# Drone_v1_0.net
KiCad netlist of a schematic drawn in Altium Designer
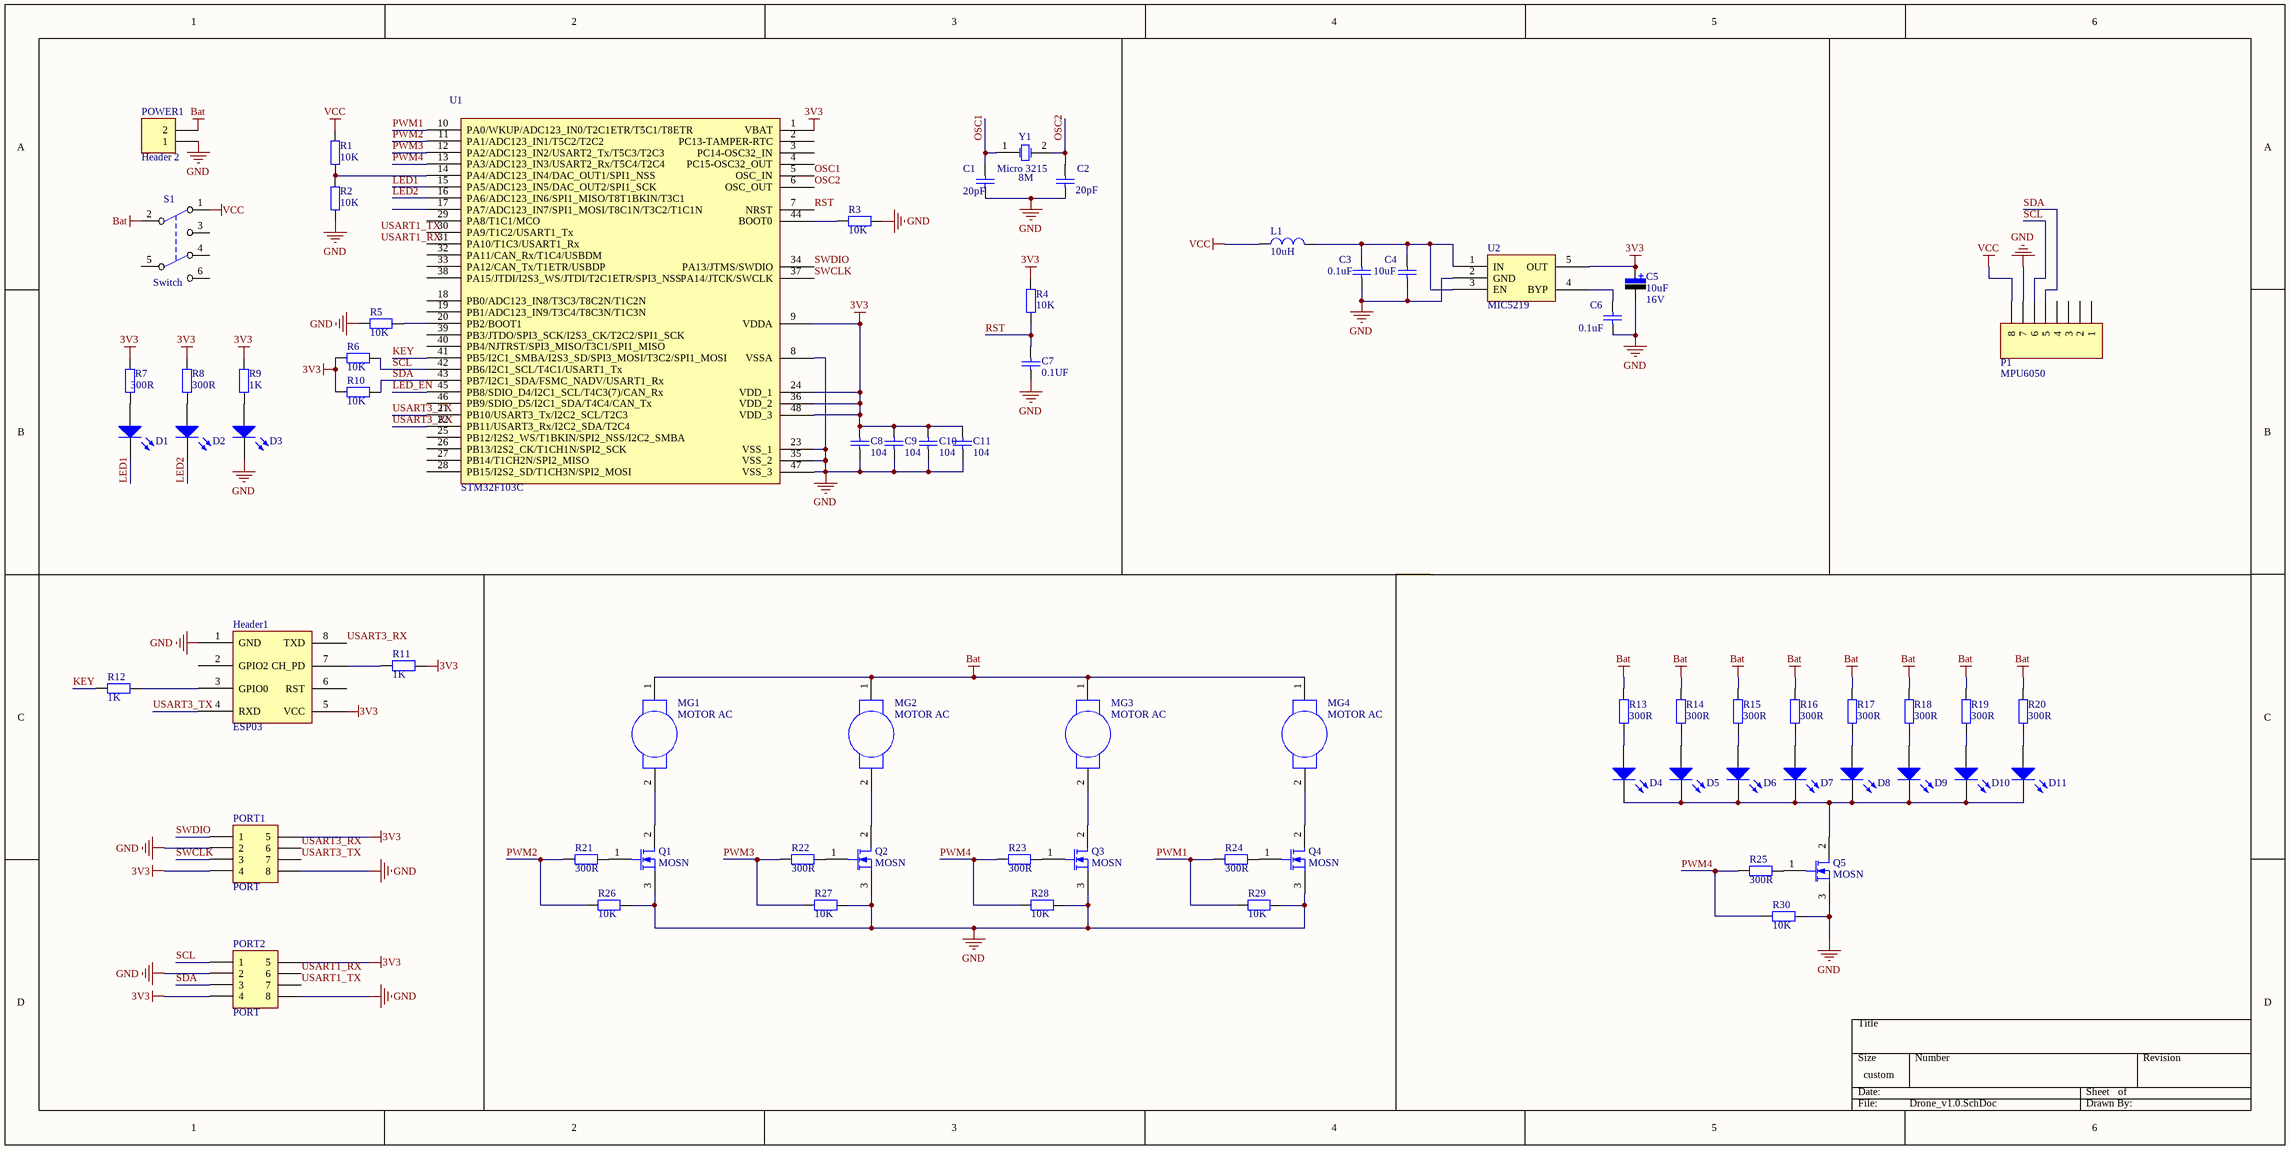
[diagram p0: Drone_v1.0.SchDoc]

(export (version "E")
  (design (tool "Eeschema 10.0.6"))
  (components
    (comp (ref "C1")
      (value "20pF")
      (footprint "0805-2")
      (description "Capacitor")
      (fields (field (name "Comment") "0402 12pF") (field (name "PUBLISHER") "Altium Limited"))
      (libsource (lib "Miscellaneous Devices") (part "Cap"))
    )
    (comp (ref "C2")
      (value "20pF")
      (footprint "0805-2")
      (description "Capacitor")
      (fields (field (name "Comment") "0402 12pF") (field (name "PUBLISHER") "Altium Limited"))
      (libsource (lib "Miscellaneous Devices") (part "Cap"))
    )
    (comp (ref "C3")
      (value "0.1uF")
      (footprint "0805-2")
      (description "Capacitor")
      (fields (field (name "Comment") "0402 12pF") (field (name "PUBLISHER") "Altium Limited"))
      (libsource (lib "Miscellaneous Devices") (part "Cap"))
    )
    (comp (ref "C4")
      (value "10uF")
      (footprint "0805-2")
      (description "Capacitor")
      (fields (field (name "Comment") "0402 12pF") (field (name "PUBLISHER") "Altium Limited"))
      (libsource (lib "Miscellaneous Devices") (part "Cap"))
    )
    (comp (ref "C5")
      (value "10uF")
      (footprint "1206")
      (description "极性电解电容")
      (fields
        (field (name "VOL") "16V")
        (field (name "Comment") "Cap Pol")
        (field (name "PUBLISHER") "Altium Limited")
      )
      (libsource (lib "Fszhang") (part "Cap Pol"))
    )
    (comp (ref "C6")
      (value "0402 12pF")
      (footprint "0805-2")
      (description "Capacitor")
      (fields (field (name "50V") "0.1uF") (field (name "PUBLISHER") "Altium Limited"))
      (libsource (lib "Miscellaneous Devices") (part "Cap"))
    )
    (comp (ref "C7")
      (value "0.1UF")
      (footprint "0805-2")
      (description "无极性电容")
      (fields (field (name "Comment") "Cap") (field (name "PUBLISHER") "Altium Limited"))
      (libsource (lib "Fszhang") (part "Cap"))
    )
    (comp (ref "C8")
      (value "104")
      (footprint "0805-2")
      (description "无极性电容")
      (fields (field (name "Comment") "Cap") (field (name "PUBLISHER") "Altium Limited"))
      (libsource (lib "Fszhang") (part "Cap"))
    )
    (comp (ref "C9")
      (value "104")
      (footprint "0805-2")
      (description "无极性电容")
      (fields (field (name "Comment") "Cap") (field (name "PUBLISHER") "Altium Limited"))
      (libsource (lib "Fszhang") (part "Cap"))
    )
    (comp (ref "C10")
      (value "104")
      (footprint "0805-2")
      (description "无极性电容")
      (fields (field (name "Comment") "Cap") (field (name "PUBLISHER") "Altium Limited"))
      (libsource (lib "Fszhang") (part "Cap"))
    )
    (comp (ref "C11")
      (value "104")
      (footprint "0805-2")
      (description "无极性电容")
      (fields (field (name "Comment") "Cap") (field (name "PUBLISHER") "Altium Limited"))
      (libsource (lib "Fszhang") (part "Cap"))
    )
    (comp (ref "D1")
      (value "LED0")
      (footprint "LED_0805")
      (description "发光二极管")
      (fields (field (name "PUBLISHER") "Altium Limited"))
      (libsource (lib "Fszhang") (part "LED0"))
    )
    (comp (ref "D2")
      (value "LED0")
      (footprint "LED_0805")
      (description "发光二极管")
      (fields (field (name "PUBLISHER") "Altium Limited"))
      (libsource (lib "Fszhang") (part "LED0"))
    )
    (comp (ref "D3")
      (value "LED0")
      (footprint "LED_0805")
      (description "发光二极管")
      (fields (field (name "PUBLISHER") "Altium Limited"))
      (libsource (lib "Fszhang") (part "LED0"))
    )
    (comp (ref "D4")
      (value "LED0")
      (footprint "LED_0805")
      (description "发光二极管")
      (fields (field (name "PUBLISHER") "Altium Limited"))
      (libsource (lib "Fszhang") (part "LED0"))
    )
    (comp (ref "D5")
      (value "LED0")
      (footprint "LED_0805")
      (description "发光二极管")
      (fields (field (name "PUBLISHER") "Altium Limited"))
      (libsource (lib "Fszhang") (part "LED0"))
    )
    (comp (ref "D6")
      (value "LED0")
      (footprint "LED_0805")
      (description "发光二极管")
      (fields (field (name "PUBLISHER") "Altium Limited"))
      (libsource (lib "Fszhang") (part "LED0"))
    )
    (comp (ref "D7")
      (value "LED0")
      (footprint "LED_0805")
      (description "发光二极管")
      (fields (field (name "PUBLISHER") "Altium Limited"))
      (libsource (lib "Fszhang") (part "LED0"))
    )
    (comp (ref "D8")
      (value "LED0")
      (footprint "LED_0805")
      (description "发光二极管")
      (fields (field (name "PUBLISHER") "Altium Limited"))
      (libsource (lib "Fszhang") (part "LED0"))
    )
    (comp (ref "D9")
      (value "LED0")
      (footprint "LED_0805")
      (description "发光二极管")
      (fields (field (name "PUBLISHER") "Altium Limited"))
      (libsource (lib "Fszhang") (part "LED0"))
    )
    (comp (ref "D10")
      (value "LED0")
      (footprint "LED_0805")
      (description "发光二极管")
      (fields (field (name "PUBLISHER") "Altium Limited"))
      (libsource (lib "Fszhang") (part "LED0"))
    )
    (comp (ref "D11")
      (value "LED0")
      (footprint "LED_0805")
      (description "发光二极管")
      (fields (field (name "PUBLISHER") "Altium Limited"))
      (libsource (lib "Fszhang") (part "LED0"))
    )
    (comp (ref "Header1")
      (value "ESP03")
      (footprint "PCBComponent_1")
      (libsource (lib "Header4") (part "Hearder"))
    )
    (comp (ref "L1")
      (value "10uH")
      (footprint "0805-1")
      (description "电感")
      (fields (field (name "Comment") "Inductor") (field (name "PUBLISHER") "Altium Limited"))
      (libsource (lib "Fszhang") (part "Inductor"))
    )
    (comp (ref "MG1") (value "MOTOR AC") (footprint "Motor") (libsource (lib "杂元件库") (part "MOTOR AC")))
    (comp (ref "MG2") (value "MOTOR AC") (footprint "Motor") (libsource (lib "杂元件库") (part "MOTOR AC")))
    (comp (ref "MG3") (value "MOTOR AC") (footprint "Motor") (libsource (lib "杂元件库") (part "MOTOR AC")))
    (comp (ref "MG4") (value "MOTOR AC") (footprint "Motor") (libsource (lib "杂元件库") (part "MOTOR AC")))
    (comp (ref "P1")
      (value "MPU6050")
      (footprint "HDR1X8")
      (description "Header, 8-Pin")
      (fields (field (name "PUBLISHER") "Altium Limited"))
      (libsource (lib "Miscellaneous Connectors") (part "Header 8"))
    )
    (comp (ref "PORT1")
      (value "PORT")
      (footprint "HDR2X4_CEN")
      (description "Header, 4-Pin, Dual row")
      (fields (field (name "PUBLISHER") "Altium Limited"))
      (libsource (lib "Miscellaneous Connectors") (part "Header 4X2A"))
    )
    (comp (ref "PORT2")
      (value "PORT")
      (footprint "HDR2X4_CEN")
      (description "Header, 4-Pin, Dual row")
      (fields (field (name "PUBLISHER") "Altium Limited"))
      (libsource (lib "Miscellaneous Connectors") (part "Header 4X2A"))
    )
    (comp (ref "POWER1")
      (value "Header 2")
      (footprint "HDR1X2")
      (description "Header, 2-Pin")
      (fields (field (name "PUBLISHER") "Altium Limited"))
      (libsource (lib "Miscellaneous Connectors") (part "Header 2"))
    )
    (comp (ref "Q1") (value "MOSN") (footprint "PCBComponent_1") (libsource (lib "MOS-N") (part "SI2302")))
    (comp (ref "Q2") (value "MOSN") (footprint "PCBComponent_1") (libsource (lib "MOS-N") (part "SI2302")))
    (comp (ref "Q3") (value "MOSN") (footprint "PCBComponent_1") (libsource (lib "MOS-N") (part "SI2302")))
    (comp (ref "Q4") (value "MOSN") (footprint "PCBComponent_1") (libsource (lib "MOS-N") (part "SI2302")))
    (comp (ref "Q5") (value "MOSN") (footprint "PCBComponent_1") (libsource (lib "MOS-N") (part "SI2302")))
    (comp (ref "R1")
      (value "10K")
      (footprint "0805-2")
      (description "贴片电阻")
      (fields (field (name "Comment") "Res1") (field (name "PUBLISHER") "Altium Limited"))
      (libsource (lib "") (part "Res1_3"))
    )
    (comp (ref "R2")
      (value "10K")
      (footprint "0805-2")
      (description "贴片电阻")
      (fields (field (name "Comment") "Res1") (field (name "PUBLISHER") "Altium Limited"))
      (libsource (lib "") (part "Res1_1"))
    )
    (comp (ref "R3")
      (value "10K")
      (footprint "0805-2")
      (description "贴片电阻")
      (fields (field (name "Comment") "Res1") (field (name "PUBLISHER") "Altium Limited"))
      (libsource (lib "") (part "Res1_2"))
    )
    (comp (ref "R4")
      (value "10K")
      (footprint "0805-2")
      (description "贴片电阻")
      (fields (field (name "Comment") "Res1") (field (name "PUBLISHER") "Altium Limited"))
      (libsource (lib "") (part "Res1_3"))
    )
    (comp (ref "R5")
      (value "10K")
      (footprint "0805-2")
      (description "贴片电阻")
      (fields (field (name "Comment") "Res1") (field (name "PUBLISHER") "Altium Limited"))
      (libsource (lib "Fszhang") (part "Res1"))
    )
    (comp (ref "R6")
      (value "10K")
      (footprint "0805-2")
      (description "贴片电阻")
      (fields (field (name "Comment") "Res1") (field (name "PUBLISHER") "Altium Limited"))
      (libsource (lib "Fszhang") (part "Res1"))
    )
    (comp (ref "R7")
      (value "300R")
      (footprint "0805-2")
      (description "贴片电阻")
      (fields (field (name "Comment") "Res1") (field (name "PUBLISHER") "Altium Limited"))
      (libsource (lib "") (part "Res1_3"))
    )
    (comp (ref "R8")
      (value "300R")
      (footprint "0805-2")
      (description "贴片电阻")
      (fields (field (name "Comment") "Res1") (field (name "PUBLISHER") "Altium Limited"))
      (libsource (lib "") (part "Res1_3"))
    )
    (comp (ref "R9")
      (value "1K")
      (footprint "0805-2")
      (description "贴片电阻")
      (fields (field (name "Comment") "Res1") (field (name "PUBLISHER") "Altium Limited"))
      (libsource (lib "") (part "Res1_3"))
    )
    (comp (ref "R10")
      (value "10K")
      (footprint "0805-2")
      (description "贴片电阻")
      (fields (field (name "Comment") "Res1") (field (name "PUBLISHER") "Altium Limited"))
      (libsource (lib "Fszhang") (part "Res1"))
    )
    (comp (ref "R11")
      (value "1K")
      (footprint "0805-2")
      (description "贴片电阻")
      (fields (field (name "Comment") "Res1") (field (name "PUBLISHER") "Altium Limited"))
      (libsource (lib "Fszhang") (part "Res1"))
    )
    (comp (ref "R12")
      (value "1K")
      (footprint "0805-2")
      (description "贴片电阻")
      (fields (field (name "Comment") "Res1") (field (name "PUBLISHER") "Altium Limited"))
      (libsource (lib "Fszhang") (part "Res1"))
    )
    (comp (ref "R13")
      (value "300R")
      (footprint "0805-2")
      (description "贴片电阻")
      (fields (field (name "Comment") "Res1") (field (name "PUBLISHER") "Altium Limited"))
      (libsource (lib "") (part "Res1_1"))
    )
    (comp (ref "R14")
      (value "300R")
      (footprint "0805-2")
      (description "贴片电阻")
      (fields (field (name "Comment") "Res1") (field (name "PUBLISHER") "Altium Limited"))
      (libsource (lib "") (part "Res1_1"))
    )
    (comp (ref "R15")
      (value "300R")
      (footprint "0805-2")
      (description "贴片电阻")
      (fields (field (name "Comment") "Res1") (field (name "PUBLISHER") "Altium Limited"))
      (libsource (lib "") (part "Res1_1"))
    )
    (comp (ref "R16")
      (value "300R")
      (footprint "0805-2")
      (description "贴片电阻")
      (fields (field (name "Comment") "Res1") (field (name "PUBLISHER") "Altium Limited"))
      (libsource (lib "") (part "Res1_1"))
    )
    (comp (ref "R17")
      (value "300R")
      (footprint "0805-2")
      (description "贴片电阻")
      (fields (field (name "Comment") "Res1") (field (name "PUBLISHER") "Altium Limited"))
      (libsource (lib "") (part "Res1_1"))
    )
    (comp (ref "R18")
      (value "300R")
      (footprint "0805-2")
      (description "贴片电阻")
      (fields (field (name "Comment") "Res1") (field (name "PUBLISHER") "Altium Limited"))
      (libsource (lib "") (part "Res1_1"))
    )
    (comp (ref "R19")
      (value "300R")
      (footprint "0805-2")
      (description "贴片电阻")
      (fields (field (name "Comment") "Res1") (field (name "PUBLISHER") "Altium Limited"))
      (libsource (lib "") (part "Res1_1"))
    )
    (comp (ref "R20")
      (value "300R")
      (footprint "0805-2")
      (description "贴片电阻")
      (fields (field (name "Comment") "Res1") (field (name "PUBLISHER") "Altium Limited"))
      (libsource (lib "") (part "Res1_1"))
    )
    (comp (ref "R21")
      (value "300R")
      (footprint "0805-2")
      (description "贴片电阻")
      (fields (field (name "Comment") "Res1") (field (name "PUBLISHER") "Altium Limited"))
      (libsource (lib "") (part "Res1_2"))
    )
    (comp (ref "R22")
      (value "300R")
      (footprint "0805-2")
      (description "贴片电阻")
      (fields (field (name "Comment") "Res1") (field (name "PUBLISHER") "Altium Limited"))
      (libsource (lib "") (part "Res1_2"))
    )
    (comp (ref "R23")
      (value "300R")
      (footprint "0805-2")
      (description "贴片电阻")
      (fields (field (name "Comment") "Res1") (field (name "PUBLISHER") "Altium Limited"))
      (libsource (lib "") (part "Res1_2"))
    )
    (comp (ref "R24")
      (value "300R")
      (footprint "0805-2")
      (description "贴片电阻")
      (fields (field (name "Comment") "Res1") (field (name "PUBLISHER") "Altium Limited"))
      (libsource (lib "") (part "Res1_2"))
    )
    (comp (ref "R25")
      (value "300R")
      (footprint "0805-2")
      (description "贴片电阻")
      (fields (field (name "Comment") "Res1") (field (name "PUBLISHER") "Altium Limited"))
      (libsource (lib "") (part "Res1_2"))
    )
    (comp (ref "R26")
      (value "10K")
      (footprint "0805-2")
      (description "贴片电阻")
      (fields (field (name "Comment") "Res1") (field (name "PUBLISHER") "Altium Limited"))
      (libsource (lib "") (part "Res1_2"))
    )
    (comp (ref "R27")
      (value "10K")
      (footprint "0805-2")
      (description "贴片电阻")
      (fields (field (name "Comment") "Res1") (field (name "PUBLISHER") "Altium Limited"))
      (libsource (lib "") (part "Res1_2"))
    )
    (comp (ref "R28")
      (value "10K")
      (footprint "0805-2")
      (description "贴片电阻")
      (fields (field (name "Comment") "Res1") (field (name "PUBLISHER") "Altium Limited"))
      (libsource (lib "") (part "Res1_2"))
    )
    (comp (ref "R29")
      (value "10K")
      (footprint "0805-2")
      (description "贴片电阻")
      (fields (field (name "Comment") "Res1") (field (name "PUBLISHER") "Altium Limited"))
      (libsource (lib "") (part "Res1_2"))
    )
    (comp (ref "R30")
      (value "10K")
      (footprint "0805-2")
      (description "贴片电阻")
      (fields (field (name "Comment") "Res1") (field (name "PUBLISHER") "Altium Limited"))
      (libsource (lib "") (part "Res1_2"))
    )
    (comp (ref "S1") (value "Switch") (footprint "开关") (libsource (lib "开关") (part "双刀双柄开关")))
    (comp (ref "U1")
      (value "STM32F103C")
      (footprint "LQFP-48_M")
      (description "STM32单片机48引脚")
      (libsource (lib "Fszhang") (part "STM32F103C"))
    )
    (comp (ref "U2") (value "MIC5219") (footprint "SOT25-5") (libsource (lib "MIC5219") (part "MIC5219")))
    (comp (ref "Y1")
      (value "Micro 3215")
      (footprint "XTAL5")
      (description "Crystal Oscillator")
      (fields (field (name "ALTIUM_VALUE") "8M"))
      (libsource (lib "Miscellaneous Devices") (part "XTAL"))
    )
  )
  (nets
    (net (code "1") (name "/KEY") (class "Default")
      (node (ref "R12") (pin "1") (pinfunction "1_1") (pintype "passive"))
      (node (ref "U1") (pin "41") (pinfunction "PB5/I2C1_SMBA/I2S3_SD/SPI3_MOSI/T3C2/SPI1_MOSI_41") (pintype "passive"))
    )
    (net (code "2") (name "/LED1") (class "Default")
      (node (ref "D1") (pin "2") (pinfunction "K_2") (pintype "passive"))
      (node (ref "U1") (pin "15") (pinfunction "PA5/ADC123_IN5/DAC_OUT2/SPI1_SCK_15") (pintype "passive"))
    )
    (net (code "3") (name "/LED2") (class "Default")
      (node (ref "D2") (pin "2") (pinfunction "K_2") (pintype "passive"))
      (node (ref "U1") (pin "16") (pinfunction "PA6/ADC123_IN6/SPI1_MISO/T8T1BKIN/T3C1_16") (pintype "passive"))
    )
    (net (code "4") (name "/LED_EN") (class "Default")
      (node (ref "U1") (pin "45") (pinfunction "PB8/SDIO_D4/I2C1_SCL/T4C3(7)/CAN_Rx_45") (pintype "passive"))
    )
    (net (code "5") (name "/OSC1") (class "Default")
      (node (ref "C1") (pin "1") (pinfunction "1_1") (pintype "passive"))
      (node (ref "U1") (pin "5") (pinfunction "OSC_IN_5") (pintype "passive"))
      (node (ref "Y1") (pin "1") (pinfunction "OSC1_1") (pintype "passive"))
    )
    (net (code "6") (name "/OSC2") (class "Default")
      (node (ref "C2") (pin "2") (pinfunction "2_2") (pintype "passive"))
      (node (ref "U1") (pin "6") (pinfunction "OSC_OUT_6") (pintype "passive"))
      (node (ref "Y1") (pin "2") (pinfunction "OSC2_2") (pintype "passive"))
    )
    (net (code "7") (name "/PWM1") (class "Default")
      (node (ref "R24") (pin "2") (pinfunction "2_2") (pintype "passive"))
      (node (ref "R29") (pin "2") (pinfunction "2_2") (pintype "passive"))
      (node (ref "U1") (pin "10") (pinfunction "PA0/WKUP/ADC123_IN0/T2C1ETR/T5C1/T8ETR_10") (pintype "passive"))
    )
    (net (code "8") (name "/PWM2") (class "Default")
      (node (ref "R21") (pin "2") (pinfunction "2_2") (pintype "passive"))
      (node (ref "R26") (pin "2") (pinfunction "2_2") (pintype "passive"))
      (node (ref "U1") (pin "11") (pinfunction "PA1/ADC123_IN1/T5C2/T2C2_11") (pintype "passive"))
    )
    (net (code "9") (name "/PWM3") (class "Default")
      (node (ref "R22") (pin "2") (pinfunction "2_2") (pintype "passive"))
      (node (ref "R27") (pin "2") (pinfunction "2_2") (pintype "passive"))
      (node (ref "U1") (pin "12") (pinfunction "PA2/ADC123_IN2/USART2_Tx/T5C3/T2C3_12") (pintype "passive"))
    )
    (net (code "10") (name "/PWM4") (class "Default")
      (node (ref "R23") (pin "2") (pinfunction "2_2") (pintype "passive"))
      (node (ref "R25") (pin "2") (pinfunction "2_2") (pintype "passive"))
      (node (ref "R28") (pin "2") (pinfunction "2_2") (pintype "passive"))
      (node (ref "R30") (pin "2") (pinfunction "2_2") (pintype "passive"))
      (node (ref "U1") (pin "13") (pinfunction "PA3/ADC123_IN3/USART2_Rx/T5C4/T2C4_13") (pintype "passive"))
    )
    (net (code "11") (name "/RST") (class "Default")
      (node (ref "C7") (pin "1") (pinfunction "1_1") (pintype "passive"))
      (node (ref "R4") (pin "1") (pinfunction "1_1") (pintype "passive"))
      (node (ref "U1") (pin "7") (pinfunction "NRST_7") (pintype "passive"))
    )
    (net (code "12") (name "/SCL") (class "Default")
      (node (ref "P1") (pin "6") (pinfunction "6_6") (pintype "passive"))
      (node (ref "PORT2") (pin "1") (pinfunction "1_1") (pintype "passive"))
      (node (ref "R6") (pin "2") (pinfunction "2_2") (pintype "passive"))
      (node (ref "U1") (pin "42") (pinfunction "PB6/I2C1_SCL/T4C1/USART1_Tx_42") (pintype "passive"))
    )
    (net (code "13") (name "/SDA") (class "Default")
      (node (ref "P1") (pin "5") (pinfunction "5_5") (pintype "passive"))
      (node (ref "PORT2") (pin "3") (pinfunction "3_3") (pintype "passive"))
      (node (ref "R10") (pin "2") (pinfunction "2_2") (pintype "passive"))
      (node (ref "U1") (pin "43") (pinfunction "PB7/I2C1_SDA/FSMC_NADV/USART1_Rx_43") (pintype "passive"))
    )
    (net (code "14") (name "/SWCLK") (class "Default")
      (node (ref "PORT1") (pin "3") (pinfunction "3_3") (pintype "passive"))
      (node (ref "U1") (pin "37") (pinfunction "PA14/JTCK/SWCLK_37") (pintype "passive"))
    )
    (net (code "15") (name "/SWDIO") (class "Default")
      (node (ref "PORT1") (pin "1") (pinfunction "1_1") (pintype "passive"))
      (node (ref "U1") (pin "34") (pinfunction "PA13/JTMS/SWDIO_34") (pintype "passive"))
    )
    (net (code "16") (name "/USART1_RX") (class "Default")
      (node (ref "PORT2") (pin "6") (pinfunction "6_6") (pintype "passive"))
    )
    (net (code "17") (name "/USART1_TX") (class "Default")
      (node (ref "PORT2") (pin "7") (pinfunction "7_7") (pintype "passive"))
    )
    (net (code "18") (name "/USART3_RX") (class "Default")
      (node (ref "Header1") (pin "8") (pinfunction "TXD_8") (pintype "passive"))
      (node (ref "PORT1") (pin "6") (pinfunction "6_6") (pintype "passive"))
      (node (ref "U1") (pin "22") (pinfunction "PB11/USART3_Rx/I2C2_SDA/T2C4_22") (pintype "passive"))
    )
    (net (code "19") (name "/USART3_TX") (class "Default")
      (node (ref "Header1") (pin "4") (pinfunction "RXD_4") (pintype "passive"))
      (node (ref "PORT1") (pin "7") (pinfunction "7_7") (pintype "passive"))
      (node (ref "U1") (pin "21") (pinfunction "PB10/USART3_Tx/I2C2_SCL/T2C3_21") (pintype "passive"))
    )
    (net (code "20") (name "3V3") (class "Default")
      (node (ref "C10") (pin "2") (pinfunction "2_2") (pintype "passive"))
      (node (ref "C11") (pin "2") (pinfunction "2_2") (pintype "passive"))
      (node (ref "C5") (pin "1") (pinfunction "1_1") (pintype "passive"))
      (node (ref "C8") (pin "2") (pinfunction "2_2") (pintype "passive"))
      (node (ref "C9") (pin "2") (pinfunction "2_2") (pintype "passive"))
      (node (ref "Header1") (pin "5") (pinfunction "VCC_5") (pintype "passive"))
      (node (ref "PORT1") (pin "4") (pinfunction "4_4") (pintype "passive"))
      (node (ref "PORT1") (pin "5") (pinfunction "5_5") (pintype "passive"))
      (node (ref "PORT2") (pin "4") (pinfunction "4_4") (pintype "passive"))
      (node (ref "PORT2") (pin "5") (pinfunction "5_5") (pintype "passive"))
      (node (ref "R10") (pin "1") (pinfunction "1_1") (pintype "passive"))
      (node (ref "R11") (pin "2") (pinfunction "2_2") (pintype "passive"))
      (node (ref "R4") (pin "2") (pinfunction "2_2") (pintype "passive"))
      (node (ref "R6") (pin "1") (pinfunction "1_1") (pintype "passive"))
      (node (ref "R7") (pin "2") (pinfunction "2_2") (pintype "passive"))
      (node (ref "R8") (pin "2") (pinfunction "2_2") (pintype "passive"))
      (node (ref "R9") (pin "2") (pinfunction "2_2") (pintype "passive"))
      (node (ref "U1") (pin "1") (pinfunction "VBAT_1") (pintype "passive"))
      (node (ref "U1") (pin "24") (pinfunction "VDD_1_24") (pintype "passive"))
      (node (ref "U1") (pin "36") (pinfunction "VDD_2_36") (pintype "passive"))
      (node (ref "U1") (pin "48") (pinfunction "VDD_3_48") (pintype "passive"))
      (node (ref "U1") (pin "9") (pinfunction "VDDA_9") (pintype "passive"))
      (node (ref "U2") (pin "5") (pinfunction "OUT_5") (pintype "passive"))
    )
    (net (code "21") (name "Bat") (class "Default")
      (node (ref "MG1") (pin "1") (pinfunction "1_1") (pintype "passive"))
      (node (ref "MG2") (pin "1") (pinfunction "1_1") (pintype "passive"))
      (node (ref "MG3") (pin "1") (pinfunction "1_1") (pintype "passive"))
      (node (ref "MG4") (pin "1") (pinfunction "1_1") (pintype "passive"))
      (node (ref "POWER1") (pin "2") (pinfunction "2_2") (pintype "passive"))
      (node (ref "R13") (pin "1") (pinfunction "1_1") (pintype "passive"))
      (node (ref "R14") (pin "1") (pinfunction "1_1") (pintype "passive"))
      (node (ref "R15") (pin "1") (pinfunction "1_1") (pintype "passive"))
      (node (ref "R16") (pin "1") (pinfunction "1_1") (pintype "passive"))
      (node (ref "R17") (pin "1") (pinfunction "1_1") (pintype "passive"))
      (node (ref "R18") (pin "1") (pinfunction "1_1") (pintype "passive"))
      (node (ref "R19") (pin "1") (pinfunction "1_1") (pintype "passive"))
      (node (ref "R20") (pin "1") (pinfunction "1_1") (pintype "passive"))
      (node (ref "S1") (pin "2") (pinfunction "COMMON1_2") (pintype "passive"))
    )
    (net (code "22") (name "GND") (class "Default")
      (node (ref "C1") (pin "2") (pinfunction "2_2") (pintype "passive"))
      (node (ref "C10") (pin "1") (pinfunction "1_1") (pintype "passive"))
      (node (ref "C11") (pin "1") (pinfunction "1_1") (pintype "passive"))
      (node (ref "C2") (pin "1") (pinfunction "1_1") (pintype "passive"))
      (node (ref "C3") (pin "2") (pinfunction "2_2") (pintype "passive"))
      (node (ref "C4") (pin "2") (pinfunction "2_2") (pintype "passive"))
      (node (ref "C5") (pin "2") (pinfunction "2_2") (pintype "passive"))
      (node (ref "C6") (pin "2") (pinfunction "2_2") (pintype "passive"))
      (node (ref "C7") (pin "2") (pinfunction "2_2") (pintype "passive"))
      (node (ref "C8") (pin "1") (pinfunction "1_1") (pintype "passive"))
      (node (ref "C9") (pin "1") (pinfunction "1_1") (pintype "passive"))
      (node (ref "D3") (pin "2") (pinfunction "K_2") (pintype "passive"))
      (node (ref "Header1") (pin "1") (pinfunction "GND_1") (pintype "passive"))
      (node (ref "P1") (pin "7") (pinfunction "7_7") (pintype "passive"))
      (node (ref "PORT1") (pin "2") (pinfunction "2_2") (pintype "passive"))
      (node (ref "PORT1") (pin "8") (pinfunction "8_8") (pintype "passive"))
      (node (ref "PORT2") (pin "2") (pinfunction "2_2") (pintype "passive"))
      (node (ref "PORT2") (pin "8") (pinfunction "8_8") (pintype "passive"))
      (node (ref "POWER1") (pin "1") (pinfunction "1_1") (pintype "passive"))
      (node (ref "Q1") (pin "3") (pinfunction "D_3") (pintype "passive"))
      (node (ref "Q2") (pin "3") (pinfunction "D_3") (pintype "passive"))
      (node (ref "Q3") (pin "3") (pinfunction "D_3") (pintype "passive"))
      (node (ref "Q4") (pin "3") (pinfunction "D_3") (pintype "passive"))
      (node (ref "Q5") (pin "3") (pinfunction "D_3") (pintype "passive"))
      (node (ref "R2") (pin "2") (pinfunction "2_2") (pintype "passive"))
      (node (ref "R26") (pin "1") (pinfunction "1_1") (pintype "passive"))
      (node (ref "R27") (pin "1") (pinfunction "1_1") (pintype "passive"))
      (node (ref "R28") (pin "1") (pinfunction "1_1") (pintype "passive"))
      (node (ref "R29") (pin "1") (pinfunction "1_1") (pintype "passive"))
      (node (ref "R3") (pin "1") (pinfunction "1_1") (pintype "passive"))
      (node (ref "R30") (pin "1") (pinfunction "1_1") (pintype "passive"))
      (node (ref "R5") (pin "1") (pinfunction "1_1") (pintype "passive"))
      (node (ref "U1") (pin "23") (pinfunction "VSS_1_23") (pintype "passive"))
      (node (ref "U1") (pin "35") (pinfunction "VSS_2_35") (pintype "passive"))
      (node (ref "U1") (pin "47") (pinfunction "VSS_3_47") (pintype "passive"))
      (node (ref "U1") (pin "8") (pinfunction "VSSA_8") (pintype "passive"))
      (node (ref "U2") (pin "2") (pinfunction "GND_2") (pintype "passive"))
    )
    (net (code "23") (name "Net-(D1-A)") (class "Default")
      (node (ref "D1") (pin "1") (pinfunction "A_1") (pintype "passive"))
      (node (ref "R7") (pin "1") (pinfunction "1_1") (pintype "passive"))
    )
    (net (code "24") (name "Net-(D2-A)") (class "Default")
      (node (ref "D2") (pin "1") (pinfunction "A_1") (pintype "passive"))
      (node (ref "R8") (pin "1") (pinfunction "1_1") (pintype "passive"))
    )
    (net (code "25") (name "Net-(D3-A)") (class "Default")
      (node (ref "D3") (pin "1") (pinfunction "A_1") (pintype "passive"))
      (node (ref "R9") (pin "1") (pinfunction "1_1") (pintype "passive"))
    )
    (net (code "26") (name "Net-(D4-A)") (class "Default")
      (node (ref "D4") (pin "1") (pinfunction "A_1") (pintype "passive"))
      (node (ref "R13") (pin "2") (pinfunction "2_2") (pintype "passive"))
    )
    (net (code "27") (name "Net-(D5-A)") (class "Default")
      (node (ref "D5") (pin "1") (pinfunction "A_1") (pintype "passive"))
      (node (ref "R14") (pin "2") (pinfunction "2_2") (pintype "passive"))
    )
    (net (code "28") (name "Net-(D6-A)") (class "Default")
      (node (ref "D6") (pin "1") (pinfunction "A_1") (pintype "passive"))
      (node (ref "R15") (pin "2") (pinfunction "2_2") (pintype "passive"))
    )
    (net (code "29") (name "Net-(D7-A)") (class "Default")
      (node (ref "D7") (pin "1") (pinfunction "A_1") (pintype "passive"))
      (node (ref "R16") (pin "2") (pinfunction "2_2") (pintype "passive"))
    )
    (net (code "30") (name "Net-(D8-A)") (class "Default")
      (node (ref "D8") (pin "1") (pinfunction "A_1") (pintype "passive"))
      (node (ref "R17") (pin "2") (pinfunction "2_2") (pintype "passive"))
    )
    (net (code "31") (name "Net-(D9-A)") (class "Default")
      (node (ref "D9") (pin "1") (pinfunction "A_1") (pintype "passive"))
      (node (ref "R18") (pin "2") (pinfunction "2_2") (pintype "passive"))
    )
    (net (code "32") (name "Net-(D10-A)") (class "Default")
      (node (ref "D10") (pin "1") (pinfunction "A_1") (pintype "passive"))
      (node (ref "R19") (pin "2") (pinfunction "2_2") (pintype "passive"))
    )
    (net (code "33") (name "Net-(D10-K)") (class "Default")
      (node (ref "D10") (pin "2") (pinfunction "K_2") (pintype "passive"))
      (node (ref "D11") (pin "2") (pinfunction "K_2") (pintype "passive"))
      (node (ref "D4") (pin "2") (pinfunction "K_2") (pintype "passive"))
      (node (ref "D5") (pin "2") (pinfunction "K_2") (pintype "passive"))
      (node (ref "D6") (pin "2") (pinfunction "K_2") (pintype "passive"))
      (node (ref "D7") (pin "2") (pinfunction "K_2") (pintype "passive"))
      (node (ref "D8") (pin "2") (pinfunction "K_2") (pintype "passive"))
      (node (ref "D9") (pin "2") (pinfunction "K_2") (pintype "passive"))
      (node (ref "Q5") (pin "2") (pinfunction "S_2") (pintype "passive"))
    )
    (net (code "34") (name "Net-(D11-A)") (class "Default")
      (node (ref "D11") (pin "1") (pinfunction "A_1") (pintype "passive"))
      (node (ref "R20") (pin "2") (pinfunction "2_2") (pintype "passive"))
    )
    (net (code "35") (name "Net-(Header1-CH_PD)") (class "Default")
      (node (ref "Header1") (pin "7") (pinfunction "CH_PD_7") (pintype "passive"))
      (node (ref "R11") (pin "1") (pinfunction "1_1") (pintype "passive"))
    )
    (net (code "36") (name "Net-(Header1-GPIO0)") (class "Default")
      (node (ref "Header1") (pin "3") (pinfunction "GPIO0_3") (pintype "passive"))
      (node (ref "R12") (pin "2") (pinfunction "2_2") (pintype "passive"))
    )
    (net (code "37") (name "Net-(Q1-G)") (class "Default")
      (node (ref "Q1") (pin "1") (pinfunction "G_1") (pintype "passive"))
      (node (ref "R21") (pin "1") (pinfunction "1_1") (pintype "passive"))
    )
    (net (code "38") (name "Net-(Q1-S)") (class "Default")
      (node (ref "MG1") (pin "2") (pinfunction "2_2") (pintype "passive"))
      (node (ref "Q1") (pin "2") (pinfunction "S_2") (pintype "passive"))
    )
    (net (code "39") (name "Net-(Q2-G)") (class "Default")
      (node (ref "Q2") (pin "1") (pinfunction "G_1") (pintype "passive"))
      (node (ref "R22") (pin "1") (pinfunction "1_1") (pintype "passive"))
    )
    (net (code "40") (name "Net-(Q2-S)") (class "Default")
      (node (ref "MG2") (pin "2") (pinfunction "2_2") (pintype "passive"))
      (node (ref "Q2") (pin "2") (pinfunction "S_2") (pintype "passive"))
    )
    (net (code "41") (name "Net-(Q3-G)") (class "Default")
      (node (ref "Q3") (pin "1") (pinfunction "G_1") (pintype "passive"))
      (node (ref "R23") (pin "1") (pinfunction "1_1") (pintype "passive"))
    )
    (net (code "42") (name "Net-(Q3-S)") (class "Default")
      (node (ref "MG3") (pin "2") (pinfunction "2_2") (pintype "passive"))
      (node (ref "Q3") (pin "2") (pinfunction "S_2") (pintype "passive"))
    )
    (net (code "43") (name "Net-(Q4-G)") (class "Default")
      (node (ref "Q4") (pin "1") (pinfunction "G_1") (pintype "passive"))
      (node (ref "R24") (pin "1") (pinfunction "1_1") (pintype "passive"))
    )
    (net (code "44") (name "Net-(Q4-S)") (class "Default")
      (node (ref "MG4") (pin "2") (pinfunction "2_2") (pintype "passive"))
      (node (ref "Q4") (pin "2") (pinfunction "S_2") (pintype "passive"))
    )
    (net (code "45") (name "Net-(Q5-G)") (class "Default")
      (node (ref "Q5") (pin "1") (pinfunction "G_1") (pintype "passive"))
      (node (ref "R25") (pin "1") (pinfunction "1_1") (pintype "passive"))
    )
    (net (code "46") (name "Net-(U1-BOOT0)") (class "Default")
      (node (ref "R3") (pin "2") (pinfunction "2_2") (pintype "passive"))
      (node (ref "U1") (pin "44") (pinfunction "BOOT0_44") (pintype "passive"))
    )
    (net (code "47") (name "Net-(U1-PA4{slash}ADC123_IN4{slash}DAC_OUT1{slash}SPI1_NSS)") (class "Default")
      (node (ref "R1") (pin "1") (pinfunction "1_1") (pintype "passive"))
      (node (ref "R2") (pin "1") (pinfunction "1_1") (pintype "passive"))
      (node (ref "U1") (pin "14") (pinfunction "PA4/ADC123_IN4/DAC_OUT1/SPI1_NSS_14") (pintype "passive"))
    )
    (net (code "48") (name "Net-(U1-PB2{slash}BOOT1)") (class "Default")
      (node (ref "R5") (pin "2") (pinfunction "2_2") (pintype "passive"))
      (node (ref "U1") (pin "20") (pinfunction "PB2/BOOT1_20") (pintype "passive"))
    )
    (net (code "49") (name "Net-(U2-BYP)") (class "Default")
      (node (ref "C6") (pin "1") (pinfunction "1_1") (pintype "passive"))
      (node (ref "U2") (pin "4") (pinfunction "BYP_4") (pintype "passive"))
    )
    (net (code "50") (name "Net-(U2-EN)") (class "Default")
      (node (ref "C3") (pin "1") (pinfunction "1_1") (pintype "passive"))
      (node (ref "C4") (pin "1") (pinfunction "1_1") (pintype "passive"))
      (node (ref "L1") (pin "2") (pinfunction "2_2") (pintype "passive"))
      (node (ref "U2") (pin "1") (pinfunction "IN_1") (pintype "passive"))
      (node (ref "U2") (pin "3") (pinfunction "EN_3") (pintype "passive"))
    )
    (net (code "51") (name "VCC") (class "Default")
      (node (ref "L1") (pin "1") (pinfunction "1_1") (pintype "passive"))
      (node (ref "P1") (pin "8") (pinfunction "8_8") (pintype "passive"))
      (node (ref "R1") (pin "2") (pinfunction "2_2") (pintype "passive"))
      (node (ref "S1") (pin "1") (pinfunction "NC1_1") (pintype "passive"))
    )
    (net (code "52") (name "unconnected-(Header1-GPIO2-Pad2)") (class "Default")
      (node (ref "Header1") (pin "2") (pinfunction "GPIO2_2") (pintype "passive"))
    )
    (net (code "53") (name "unconnected-(Header1-RST-Pad6)") (class "Default")
      (node (ref "Header1") (pin "6") (pinfunction "RST_6") (pintype "passive"))
    )
    (net (code "54") (name "unconnected-(P1-Pad1)") (class "Default")
      (node (ref "P1") (pin "1") (pinfunction "1_1") (pintype "passive"))
    )
    (net (code "55") (name "unconnected-(P1-Pad2)") (class "Default")
      (node (ref "P1") (pin "2") (pinfunction "2_2") (pintype "passive"))
    )
    (net (code "56") (name "unconnected-(P1-Pad3)") (class "Default")
      (node (ref "P1") (pin "3") (pinfunction "3_3") (pintype "passive"))
    )
    (net (code "57") (name "unconnected-(P1-Pad4)") (class "Default")
      (node (ref "P1") (pin "4") (pinfunction "4_4") (pintype "passive"))
    )
    (net (code "58") (name "unconnected-(S1-COMMON2-Pad5)") (class "Default")
      (node (ref "S1") (pin "5") (pinfunction "COMMON2_5") (pintype "passive"))
    )
    (net (code "59") (name "unconnected-(S1-NC2-Pad4)") (class "Default")
      (node (ref "S1") (pin "4") (pinfunction "NC2_4") (pintype "passive"))
    )
    (net (code "60") (name "unconnected-(S1-NO1-Pad3)") (class "Default")
      (node (ref "S1") (pin "3") (pinfunction "NO1_3") (pintype "passive"))
    )
    (net (code "61") (name "unconnected-(S1-NO2-Pad6)") (class "Default")
      (node (ref "S1") (pin "6") (pinfunction "NO2_6") (pintype "passive"))
    )
    (net (code "62") (name "unconnected-(U1-PA7{slash}ADC123_IN7{slash}SPI1_MOSI{slash}T8C1N{slash}T3C2{slash}T1C1N-Pad17)") (class "Default")
      (node (ref "U1") (pin "17") (pinfunction "PA7/ADC123_IN7/SPI1_MOSI/T8C1N/T3C2/T1C1N_17") (pintype "passive"))
    )
    (net (code "63") (name "unconnected-(U1-PA8{slash}T1C1{slash}MCO-Pad29)") (class "Default")
      (node (ref "U1") (pin "29") (pinfunction "PA8/T1C1/MCO_29") (pintype "passive"))
    )
    (net (code "64") (name "unconnected-(U1-PA9{slash}T1C2{slash}USART1_Tx-Pad30)") (class "Default")
      (node (ref "U1") (pin "30") (pinfunction "PA9/T1C2/USART1_Tx_30") (pintype "passive"))
    )
    (net (code "65") (name "unconnected-(U1-PA10{slash}T1C3{slash}USART1_Rx-Pad31)") (class "Default")
      (node (ref "U1") (pin "31") (pinfunction "PA10/T1C3/USART1_Rx_31") (pintype "passive"))
    )
    (net (code "66") (name "unconnected-(U1-PA11{slash}CAN_Rx{slash}T1C4{slash}USBDM-Pad32)") (class "Default")
      (node (ref "U1") (pin "32") (pinfunction "PA11/CAN_Rx/T1C4/USBDM_32") (pintype "passive"))
    )
    (net (code "67") (name "unconnected-(U1-PA12{slash}CAN_Tx{slash}T1ETR{slash}USBDP-Pad33)") (class "Default")
      (node (ref "U1") (pin "33") (pinfunction "PA12/CAN_Tx/T1ETR/USBDP_33") (pintype "passive"))
    )
    (net (code "68") (name "unconnected-(U1-PA15{slash}JTDI{slash}I2S3_WS{slash}JTDI{slash}T2C1ETR{slash}SPI3_NSS-Pad38)") (class "Default")
      (node (ref "U1") (pin "38") (pinfunction "PA15/JTDI/I2S3_WS/JTDI/T2C1ETR/SPI3_NSS_38") (pintype "passive"))
    )
    (net (code "69") (name "unconnected-(U1-PB0{slash}ADC123_IN8{slash}T3C3{slash}T8C2N{slash}T1C2N-Pad18)") (class "Default")
      (node (ref "U1") (pin "18") (pinfunction "PB0/ADC123_IN8/T3C3/T8C2N/T1C2N_18") (pintype "passive"))
    )
    (net (code "70") (name "unconnected-(U1-PB1{slash}ADC123_IN9{slash}T3C4{slash}T8C3N{slash}T1C3N-Pad19)") (class "Default")
      (node (ref "U1") (pin "19") (pinfunction "PB1/ADC123_IN9/T3C4/T8C3N/T1C3N_19") (pintype "passive"))
    )
    (net (code "71") (name "unconnected-(U1-PB3{slash}JTDO{slash}SPI3_SCK{slash}I2S3_CK{slash}T2C2{slash}SPI1_SCK-Pad39)") (class "Default")
      (node (ref "U1") (pin "39") (pinfunction "PB3/JTDO/SPI3_SCK/I2S3_CK/T2C2/SPI1_SCK_39") (pintype "passive"))
    )
    (net (code "72") (name "unconnected-(U1-PB4{slash}NJTRST{slash}SPI3_MISO{slash}T3C1{slash}SPI1_MISO-Pad40)") (class "Default")
      (node (ref "U1") (pin "40") (pinfunction "PB4/NJTRST/SPI3_MISO/T3C1/SPI1_MISO_40") (pintype "passive"))
    )
    (net (code "73") (name "unconnected-(U1-PB9{slash}SDIO_D5{slash}I2C1_SDA{slash}T4C4{slash}CAN_Tx-Pad46)") (class "Default")
      (node (ref "U1") (pin "46") (pinfunction "PB9/SDIO_D5/I2C1_SDA/T4C4/CAN_Tx_46") (pintype "passive"))
    )
    (net (code "74") (name "unconnected-(U1-PB12{slash}I2S2_WS{slash}T1BKIN{slash}SPI2_NSS{slash}I2C2_SMBA-Pad25)") (class "Default")
      (node (ref "U1") (pin "25") (pinfunction "PB12/I2S2_WS/T1BKIN/SPI2_NSS/I2C2_SMBA_25") (pintype "passive"))
    )
    (net (code "75") (name "unconnected-(U1-PB13{slash}I2S2_CK{slash}T1CH1N{slash}SPI2_SCK-Pad26)") (class "Default")
      (node (ref "U1") (pin "26") (pinfunction "PB13/I2S2_CK/T1CH1N/SPI2_SCK_26") (pintype "passive"))
    )
    (net (code "76") (name "unconnected-(U1-PB14{slash}T1CH2N{slash}SPI2_MISO-Pad27)") (class "Default")
      (node (ref "U1") (pin "27") (pinfunction "PB14/T1CH2N/SPI2_MISO_27") (pintype "passive"))
    )
    (net (code "77") (name "unconnected-(U1-PB15{slash}I2S2_SD{slash}T1CH3N{slash}SPI2_MOSI-Pad28)") (class "Default")
      (node (ref "U1") (pin "28") (pinfunction "PB15/I2S2_SD/T1CH3N/SPI2_MOSI_28") (pintype "passive"))
    )
    (net (code "78") (name "unconnected-(U1-PC13-TAMPER-RTC-Pad2)") (class "Default")
      (node (ref "U1") (pin "2") (pinfunction "PC13-TAMPER-RTC_2") (pintype "passive"))
    )
    (net (code "79") (name "unconnected-(U1-PC14-OSC32_IN-Pad3)") (class "Default")
      (node (ref "U1") (pin "3") (pinfunction "PC14-OSC32_IN_3") (pintype "passive"))
    )
    (net (code "80") (name "unconnected-(U1-PC15-OSC32_OUT-Pad4)") (class "Default")
      (node (ref "U1") (pin "4") (pinfunction "PC15-OSC32_OUT_4") (pintype "passive"))
    )
  )
)
